# ModuleBoard_Interface.net
KiCad netlist of a schematic drawn in Altium Designer
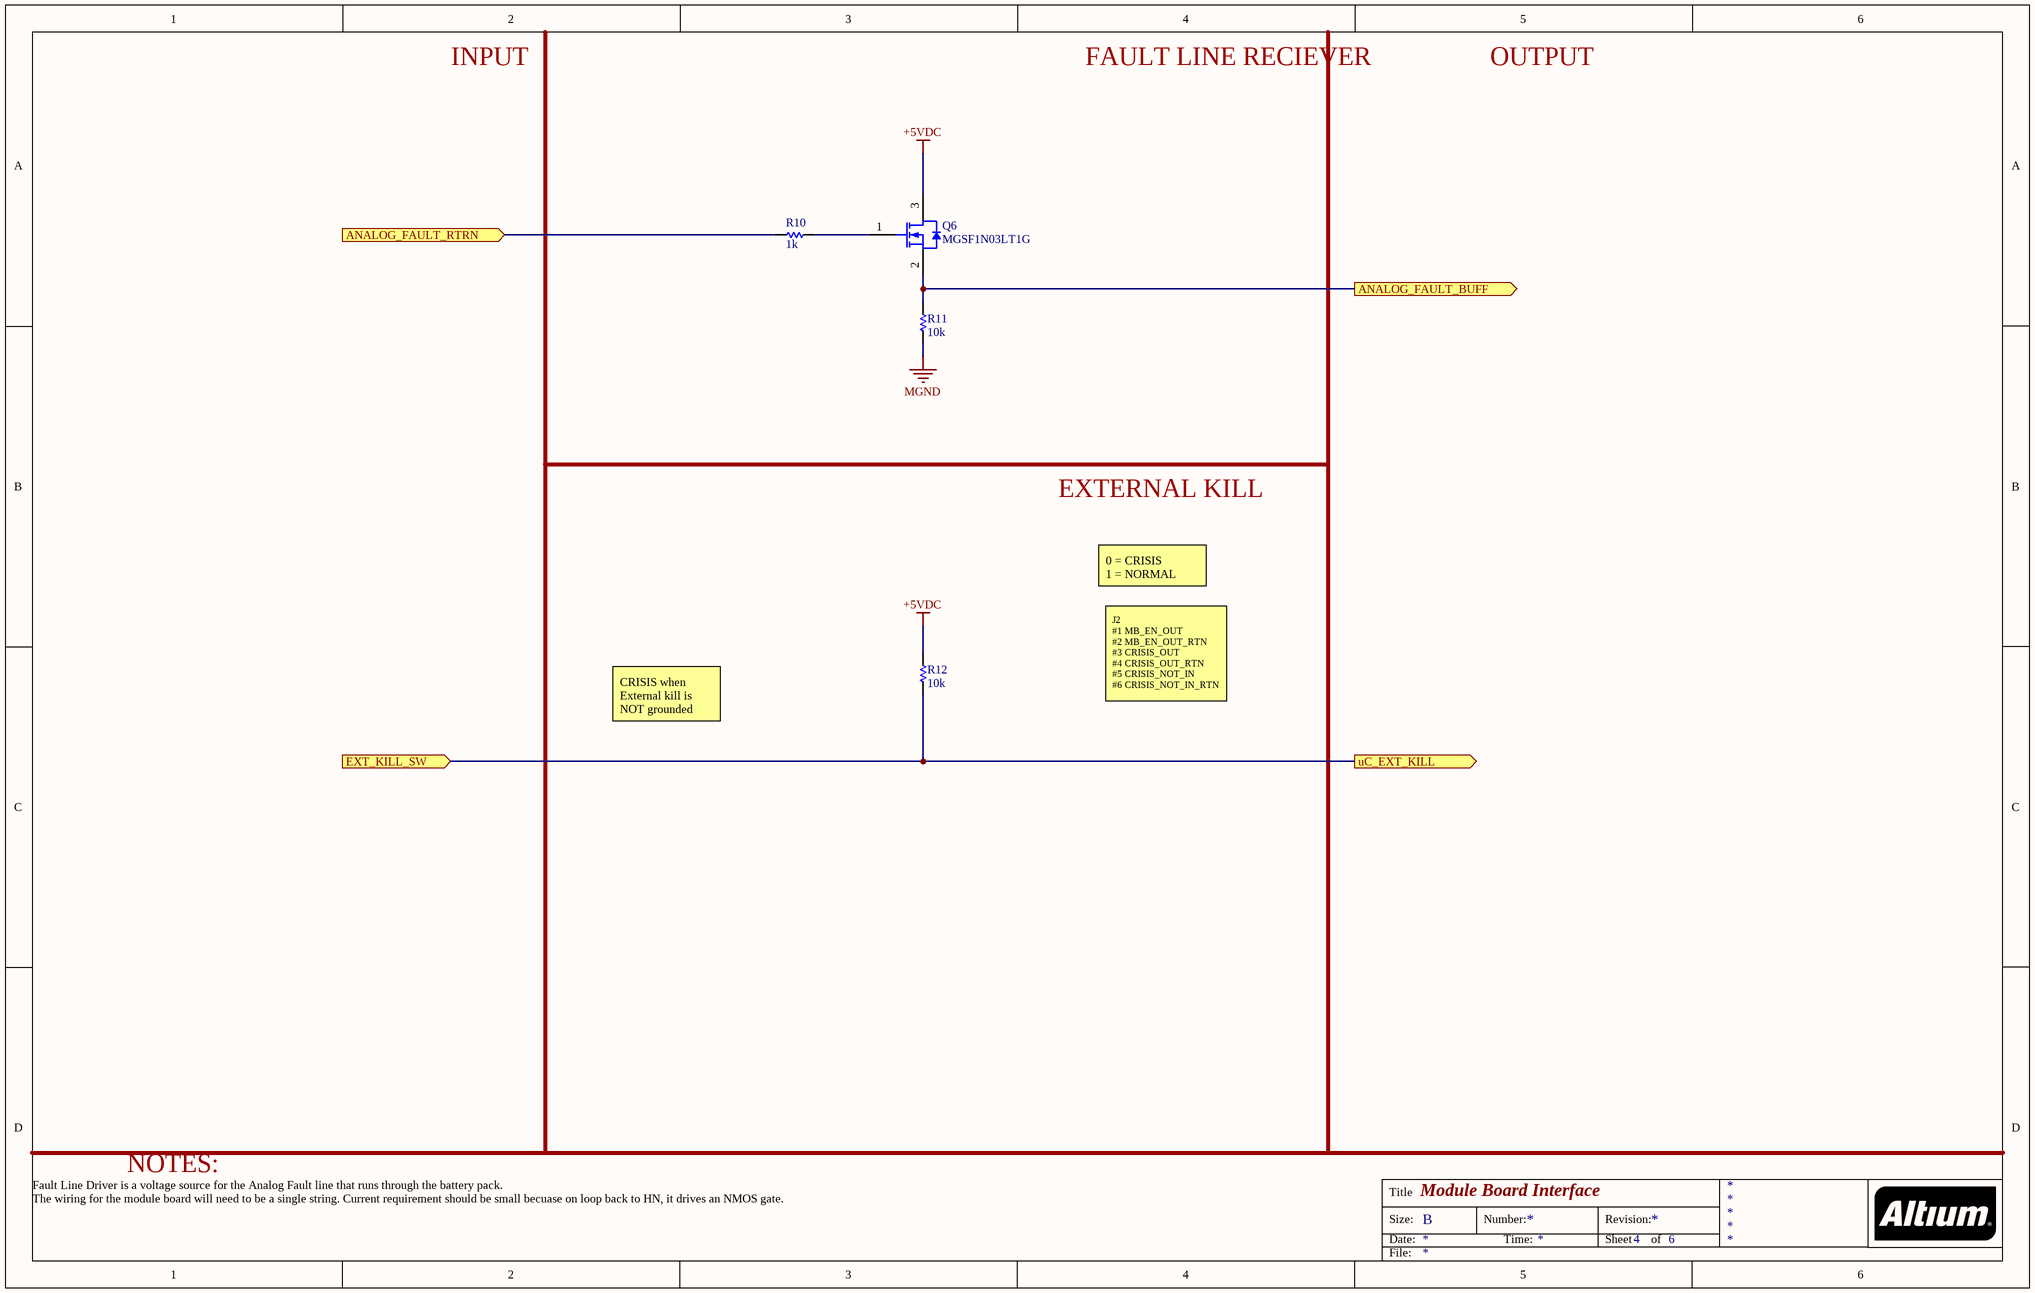
[diagram p0: ModuleBoard_Interface.SchDoc]

(export (version "E")
  (design (tool "Eeschema 10.0.6"))
  (components
    (comp (ref "Q6")
      (value "MGSF1N03LT1G")
      (footprint "ONSC-SOT-23-3-318-08_V")
      (description "Power MOSFET, 30 V, 2.1 A, Single N-Channel, 3-Pin SOT-23, Pb-Free, Tape and Reel")
      (fields (field (name "MANUFACTURER") "On Semiconductor"))
      (libsource (lib "Altium Content Vault") (part "ONSC-NMOS-G1S2D3-3"))
    )
    (comp (ref "R10")
      (value "RES_1k_1%_0603")
      (footprint "R_0603")
      (fields
        (field (name "MANUFACTURER PART NUMBER") "RC0603FR-071KL")
        (field (name "MANUFACTURER") "Yageo")
        (field (name "DIGIKEY PART NUMBER") "311-1.00KHRCT-ND")
        (field (name "SCHEMATICINFORMATION") "1k")
      )
      (libsource (lib "Resistors") (part "RES_1k_1%_0603"))
    )
    (comp (ref "R11")
      (value "RES_10k_1%_0603")
      (footprint "R_0603")
      (fields
        (field (name "MANUFACTURER PART NUMBER") "RC0603FR-0710KL")
        (field (name "MANUFACTURER") "Yageo")
        (field (name "DIGIKEY PART NUMBER") "311-10.0KHRCT-ND")
        (field (name "SCHEMATICINFORMATION") "10k")
      )
      (libsource (lib "Resistors") (part "RES_10k_1%_0603"))
    )
    (comp (ref "R12")
      (value "RES_10k_1%_0603")
      (footprint "R_0603")
      (fields
        (field (name "MANUFACTURER PART NUMBER") "RC0603FR-0710KL")
        (field (name "MANUFACTURER") "Yageo")
        (field (name "DIGIKEY PART NUMBER") "311-10.0KHRCT-ND")
        (field (name "SCHEMATICINFORMATION") "10k")
      )
      (libsource (lib "Resistors") (part "RES_10k_1%_0603"))
    )
  )
  (nets
    (net (code "1") (name "+5VDC") (class "Default")
      (node (ref "Q6") (pin "3") (pinfunction "D_3") (pintype "passive"))
      (node (ref "R12") (pin "2") (pinfunction "2_2") (pintype "passive"))
    )
    (net (code "2") (name "/ANALOG_FAULT_BUFF") (class "Default")
      (node (ref "Q6") (pin "2") (pinfunction "S_2") (pintype "passive"))
      (node (ref "R11") (pin "2") (pinfunction "2_2") (pintype "passive"))
    )
    (net (code "3") (name "/ANALOG_FAULT_RTRN") (class "Default")
      (node (ref "R10") (pin "1") (pinfunction "1_1") (pintype "passive"))
    )
    (net (code "4") (name "/EXT_KILL_SW") (class "Default")
      (node (ref "R12") (pin "1") (pinfunction "1_1") (pintype "passive"))
    )
    (net (code "5") (name "MGND") (class "Default")
      (node (ref "R11") (pin "1") (pinfunction "1_1") (pintype "passive"))
    )
    (net (code "6") (name "Net-(Q6-G)") (class "Default")
      (node (ref "Q6") (pin "1") (pinfunction "G_1") (pintype "passive"))
      (node (ref "R10") (pin "2") (pinfunction "2_2") (pintype "passive"))
    )
  )
)
